# USBGpib_biggercomponents.net
KiCad netlist of a schematic drawn in EAGLE
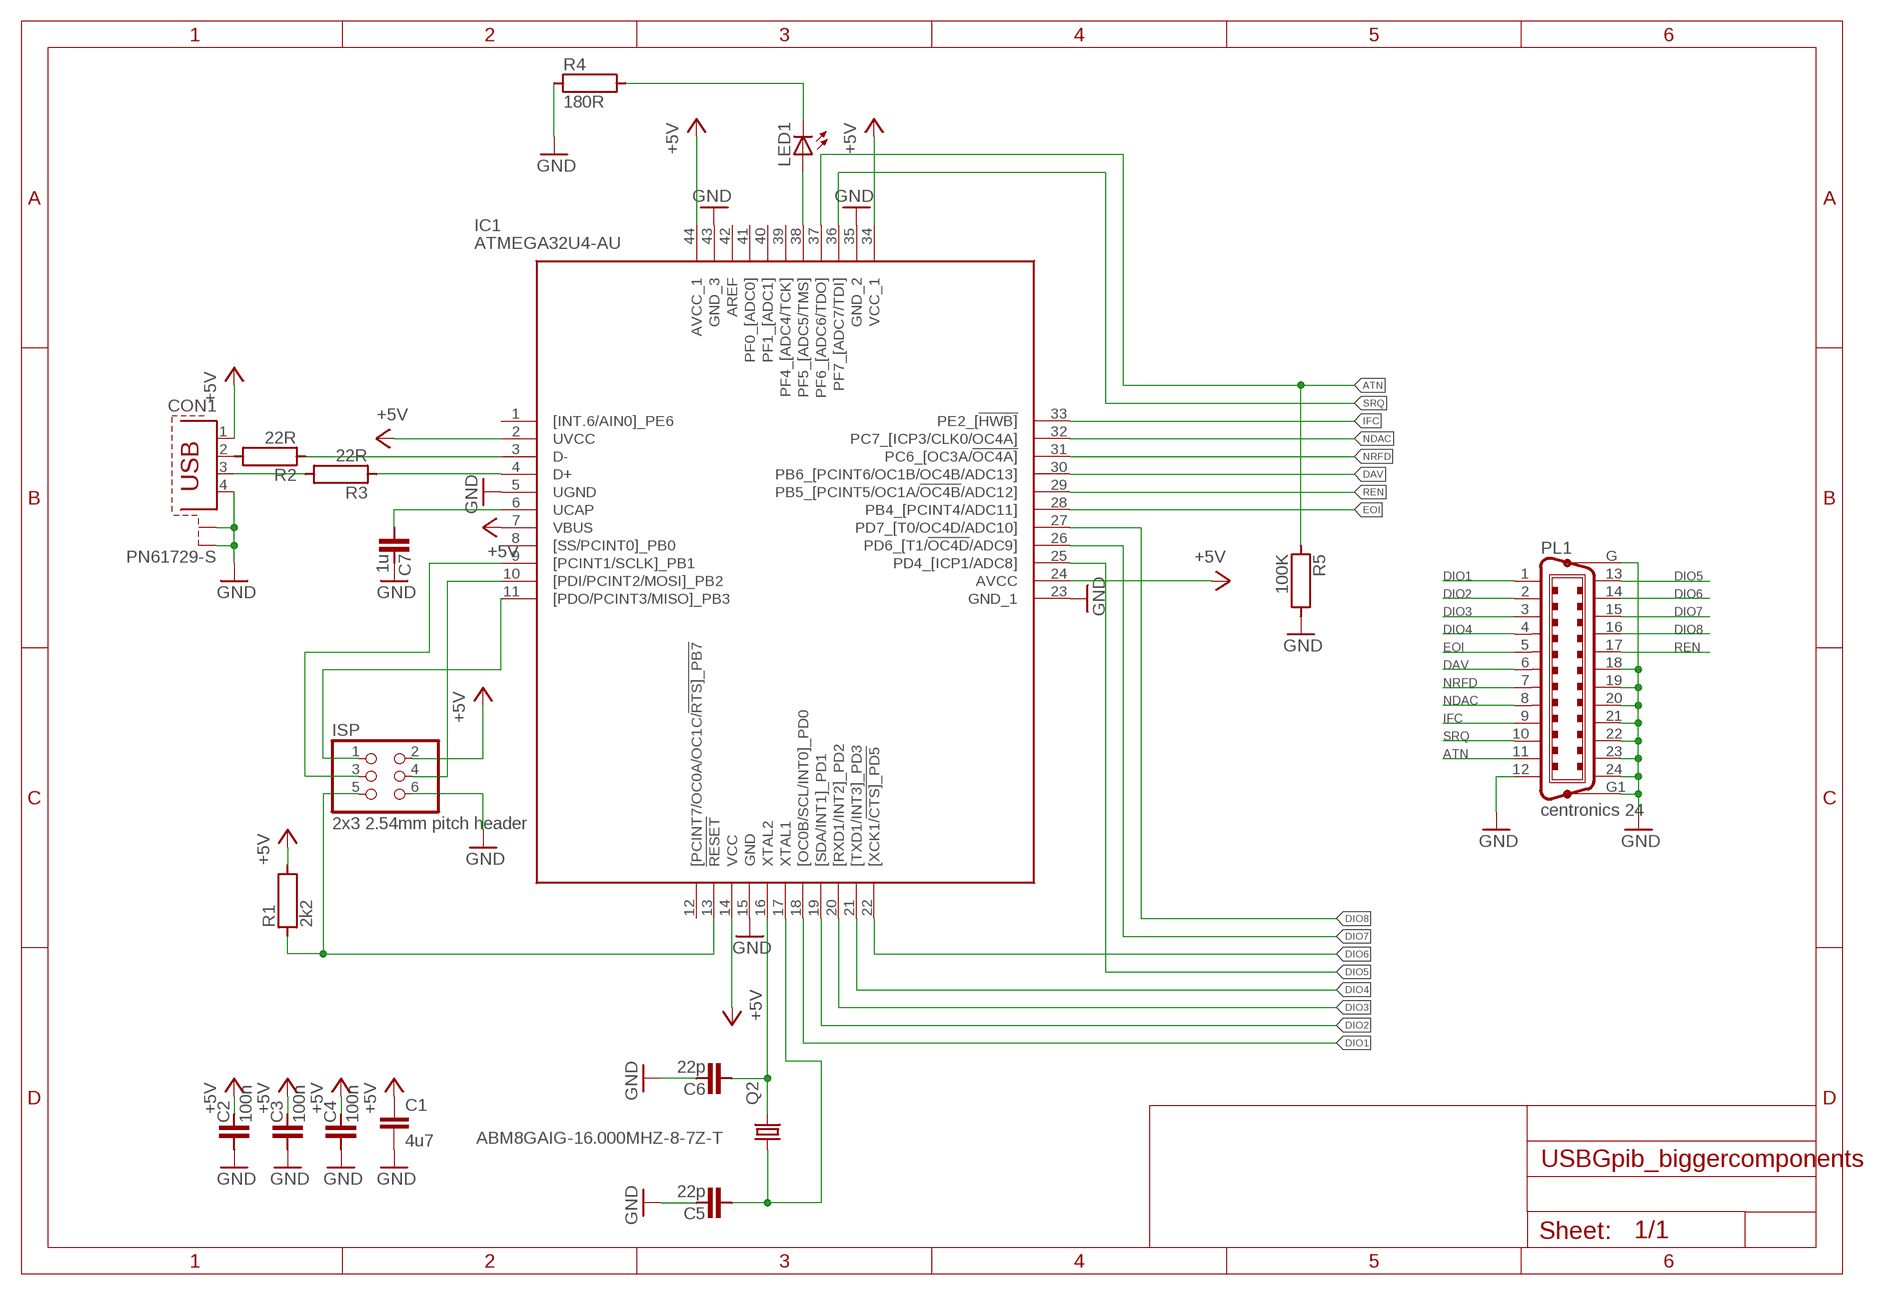
[diagram p0: schematic, sheet 1]

(export (version "E")
  (design (tool "Eeschema 10.0.6"))
  (components
    (comp (ref "C1")
      (value "4u7")
      (footprint "eagle-import:C0805")
      (libsource (lib "eagle-import") (part "C-EUC0805"))
    )
    (comp (ref "C2")
      (value "100n")
      (footprint "eagle-import:C0603")
      (libsource (lib "eagle-import") (part "C0603"))
    )
    (comp (ref "C3")
      (value "100n")
      (footprint "eagle-import:C0603")
      (libsource (lib "eagle-import") (part "C0603"))
    )
    (comp (ref "C4")
      (value "100n")
      (footprint "eagle-import:C0603")
      (libsource (lib "eagle-import") (part "C0603"))
    )
    (comp (ref "C5")
      (value "22p")
      (footprint "eagle-import:C0603")
      (libsource (lib "eagle-import") (part "C0603"))
    )
    (comp (ref "C6")
      (value "22p")
      (footprint "eagle-import:C0603")
      (libsource (lib "eagle-import") (part "C0603"))
    )
    (comp (ref "C7")
      (value "1u")
      (footprint "eagle-import:C0603")
      (libsource (lib "eagle-import") (part "C0603"))
    )
    (comp (ref "CON1")
      (value "PN61729-S")
      (footprint "eagle-import:PN61729-S")
      (libsource (lib "eagle-import") (part "PN61729-S"))
    )
    (comp (ref "IC1")
      (value "ATMEGA32U4-AU")
      (footprint "eagle-import:QFP80P1200X1200X120-44N")
      (fields
        (field (name "MANUFACTURER_PART_NUMBER") "ATMEGA16U4-AU")
        (field (name "MOUSER_PART_NUMBER") "556-ATMEGA16U4-AU")
        (field (name "RS_PART_NUMBER") "1773649P")
      )
      (libsource (lib "eagle-import") (part "ATMEGA16U4-AU"))
    )
    (comp (ref "ISP")
      (value "2x3 2.54mm pitch header")
      (footprint "eagle-import:2X03")
      (libsource (lib "eagle-import") (part "PINHD-2X3"))
    )
    (comp (ref "LED1")
      (value "LEDCHIPLED_1206")
      (footprint "eagle-import:CHIPLED_1206")
      (libsource (lib "eagle-import") (part "LEDCHIPLED_1206"))
    )
    (comp (ref "PL1")
      (value "centronics 24")
      (footprint "eagle-import:24HP_MALE")
      (libsource (lib "eagle-import") (part "C24HPMALE"))
    )
    (comp (ref "Q2")
      (value "ABM8GAIG-16.000MHZ-8-7Z-T")
      (footprint "eagle-import:3.2X2.5_KX-7")
      (libsource (lib "eagle-import") (part "KX-7"))
    )
    (comp (ref "R1")
      (value "2k2")
      (footprint "eagle-import:R0603")
      (libsource (lib "eagle-import") (part "R0603"))
    )
    (comp (ref "R2")
      (value "22R")
      (footprint "eagle-import:R0603")
      (libsource (lib "eagle-import") (part "R0603"))
    )
    (comp (ref "R3")
      (value "22R")
      (footprint "eagle-import:R0603")
      (libsource (lib "eagle-import") (part "R0603"))
    )
    (comp (ref "R4")
      (value "180R")
      (footprint "eagle-import:R0603")
      (libsource (lib "eagle-import") (part "R0603"))
    )
    (comp (ref "R5")
      (value "100K")
      (footprint "eagle-import:R0603")
      (libsource (lib "eagle-import") (part "R0603"))
    )
  )
  (nets
    (net (code "1") (name "+5V") (class "Default")
      (node (ref "C1") (pin "1") (pinfunction "1_1") (pintype "passive"))
      (node (ref "C2") (pin "2") (pinfunction "2_2") (pintype "passive"))
      (node (ref "C3") (pin "2") (pinfunction "2_2") (pintype "passive"))
      (node (ref "C4") (pin "2") (pinfunction "2_2") (pintype "passive"))
      (node (ref "CON1") (pin "1") (pinfunction "1_1") (pintype "passive"))
      (node (ref "IC1") (pin "14") (pinfunction "VCC_14") (pintype "power_in"))
      (node (ref "IC1") (pin "2") (pinfunction "UVCC_2") (pintype "power_in"))
      (node (ref "IC1") (pin "24") (pinfunction "AVCC_24") (pintype "power_in"))
      (node (ref "IC1") (pin "34") (pinfunction "VCC_1_34") (pintype "power_in"))
      (node (ref "IC1") (pin "44") (pinfunction "AVCC_1_44") (pintype "power_in"))
      (node (ref "IC1") (pin "7") (pinfunction "VBUS_7") (pintype "bidirectional"))
      (node (ref "ISP") (pin "2") (pinfunction "2_2") (pintype "passive"))
      (node (ref "R1") (pin "2") (pinfunction "2_2") (pintype "passive"))
    )
    (net (code "2") (name "ATN") (class "Default")
      (node (ref "IC1") (pin "37") (pinfunction "PF6_[ADC6/TDO]_37") (pintype "bidirectional"))
      (node (ref "PL1") (pin "11") (pinfunction "11_11") (pintype "passive"))
      (node (ref "R5") (pin "1") (pinfunction "1_1") (pintype "passive"))
    )
    (net (code "3") (name "DAV") (class "Default")
      (node (ref "IC1") (pin "30") (pinfunction "PB6_[PCINT6/OC1B/OC4B/ADC13]_30") (pintype "input"))
      (node (ref "PL1") (pin "6") (pinfunction "6_6") (pintype "passive"))
    )
    (net (code "4") (name "DIO1") (class "Default")
      (node (ref "IC1") (pin "18") (pinfunction "[OC0B/SCL/INT0]_PD0_18") (pintype "input"))
      (node (ref "PL1") (pin "1") (pinfunction "1_1") (pintype "passive"))
    )
    (net (code "5") (name "DIO2") (class "Default")
      (node (ref "IC1") (pin "19") (pinfunction "[SDA/INT1]_PD1_19") (pintype "input"))
      (node (ref "PL1") (pin "2") (pinfunction "2_2") (pintype "passive"))
    )
    (net (code "6") (name "DIO3") (class "Default")
      (node (ref "IC1") (pin "20") (pinfunction "[RXD1/INT2]_PD2_20") (pintype "input"))
      (node (ref "PL1") (pin "3") (pinfunction "3_3") (pintype "passive"))
    )
    (net (code "7") (name "DIO4") (class "Default")
      (node (ref "IC1") (pin "21") (pinfunction "[TXD1/INT3]_PD3_21") (pintype "input"))
      (node (ref "PL1") (pin "4") (pinfunction "4_4") (pintype "passive"))
    )
    (net (code "8") (name "DIO5") (class "Default")
      (node (ref "IC1") (pin "25") (pinfunction "PD4_[ICP1/ADC8]_25") (pintype "bidirectional"))
      (node (ref "PL1") (pin "13") (pinfunction "13_13") (pintype "passive"))
    )
    (net (code "9") (name "DIO6") (class "Default")
      (node (ref "IC1") (pin "22") (pinfunction "[XCK1/~{CTS]_PD5}_22") (pintype "bidirectional"))
      (node (ref "PL1") (pin "14") (pinfunction "14_14") (pintype "passive"))
    )
    (net (code "10") (name "DIO7") (class "Default")
      (node (ref "IC1") (pin "26") (pinfunction "PD6_[T1/~{OC4D}/ADC9]_26") (pintype "bidirectional"))
      (node (ref "PL1") (pin "15") (pinfunction "15_15") (pintype "passive"))
    )
    (net (code "11") (name "DIO8") (class "Default")
      (node (ref "IC1") (pin "27") (pinfunction "PD7_[T0/OC4D/ADC10]_27") (pintype "bidirectional"))
      (node (ref "PL1") (pin "16") (pinfunction "16_16") (pintype "passive"))
    )
    (net (code "12") (name "EOI") (class "Default")
      (node (ref "IC1") (pin "28") (pinfunction "PB4_[PCINT4/ADC11]_28") (pintype "input"))
      (node (ref "PL1") (pin "5") (pinfunction "5_5") (pintype "passive"))
    )
    (net (code "13") (name "GND") (class "Default")
      (node (ref "C1") (pin "2") (pinfunction "2_2") (pintype "passive"))
      (node (ref "C2") (pin "1") (pinfunction "1_1") (pintype "passive"))
      (node (ref "C3") (pin "1") (pinfunction "1_1") (pintype "passive"))
      (node (ref "C4") (pin "1") (pinfunction "1_1") (pintype "passive"))
      (node (ref "C5") (pin "2") (pinfunction "2_2") (pintype "passive"))
      (node (ref "C6") (pin "2") (pinfunction "2_2") (pintype "passive"))
      (node (ref "C7") (pin "2") (pinfunction "2_2") (pintype "passive"))
      (node (ref "CON1") (pin "4") (pinfunction "4_4") (pintype "passive"))
      (node (ref "CON1") (pin "S1") (pinfunction "S1_S1") (pintype "passive"))
      (node (ref "CON1") (pin "S2") (pinfunction "S2_S2") (pintype "passive"))
      (node (ref "IC1") (pin "15") (pinfunction "GND_15") (pintype "power_in"))
      (node (ref "IC1") (pin "23") (pinfunction "GND_1_23") (pintype "power_in"))
      (node (ref "IC1") (pin "35") (pinfunction "GND_2_35") (pintype "power_in"))
      (node (ref "IC1") (pin "43") (pinfunction "GND_3_43") (pintype "power_in"))
      (node (ref "IC1") (pin "5") (pinfunction "UGND_5") (pintype "power_in"))
      (node (ref "ISP") (pin "6") (pinfunction "6_6") (pintype "passive"))
      (node (ref "PL1") (pin "12") (pinfunction "12_12") (pintype "passive"))
      (node (ref "PL1") (pin "18") (pinfunction "18_18") (pintype "passive"))
      (node (ref "PL1") (pin "19") (pinfunction "19_19") (pintype "passive"))
      (node (ref "PL1") (pin "20") (pinfunction "20_20") (pintype "passive"))
      (node (ref "PL1") (pin "21") (pinfunction "21_21") (pintype "passive"))
      (node (ref "PL1") (pin "22") (pinfunction "22_22") (pintype "passive"))
      (node (ref "PL1") (pin "23") (pinfunction "23_23") (pintype "passive"))
      (node (ref "PL1") (pin "24") (pinfunction "24_24") (pintype "passive"))
      (node (ref "PL1") (pin "G") (pinfunction "G_G") (pintype "passive"))
      (node (ref "PL1") (pin "G1") (pinfunction "G1_G1") (pintype "passive"))
      (node (ref "R4") (pin "1") (pinfunction "1_1") (pintype "passive"))
      (node (ref "R5") (pin "2") (pinfunction "2_2") (pintype "passive"))
    )
    (net (code "14") (name "IFC") (class "Default")
      (node (ref "IC1") (pin "33") (pinfunction "PE2_[~{HWB]}_33") (pintype "bidirectional"))
      (node (ref "PL1") (pin "9") (pinfunction "9_9") (pintype "passive"))
    )
    (net (code "15") (name "NDAC") (class "Default")
      (node (ref "IC1") (pin "32") (pinfunction "PC7_[ICP3/CLK0/OC4A]_32") (pintype "input"))
      (node (ref "PL1") (pin "8") (pinfunction "8_8") (pintype "passive"))
    )
    (net (code "16") (name "NRFD") (class "Default")
      (node (ref "IC1") (pin "31") (pinfunction "PC6_[OC3A/~{OC4A]}_31") (pintype "bidirectional"))
      (node (ref "PL1") (pin "7") (pinfunction "7_7") (pintype "passive"))
    )
    (net (code "17") (name "Net-(CON1-Pad2)") (class "Default")
      (node (ref "CON1") (pin "2") (pinfunction "2_2") (pintype "passive"))
      (node (ref "R2") (pin "2") (pinfunction "2_2") (pintype "passive"))
    )
    (net (code "18") (name "Net-(CON1-Pad3)") (class "Default")
      (node (ref "CON1") (pin "3") (pinfunction "3_3") (pintype "passive"))
      (node (ref "R3") (pin "2") (pinfunction "2_2") (pintype "passive"))
    )
    (net (code "19") (name "Net-(IC1-D+)") (class "Default")
      (node (ref "IC1") (pin "4") (pinfunction "D+_4") (pintype "bidirectional"))
      (node (ref "R3") (pin "1") (pinfunction "1_1") (pintype "passive"))
    )
    (net (code "20") (name "Net-(IC1-D-)") (class "Default")
      (node (ref "IC1") (pin "3") (pinfunction "D-_3") (pintype "bidirectional"))
      (node (ref "R2") (pin "1") (pinfunction "1_1") (pintype "passive"))
    )
    (net (code "21") (name "Net-(IC1-PF5_[ADC5{slash}TMS])") (class "Default")
      (node (ref "IC1") (pin "38") (pinfunction "PF5_[ADC5/TMS]_38") (pintype "bidirectional"))
      (node (ref "LED1") (pin "A") (pinfunction "A_A") (pintype "passive"))
    )
    (net (code "22") (name "Net-(IC1-UCAP)") (class "Default")
      (node (ref "C7") (pin "1") (pinfunction "1_1") (pintype "passive"))
      (node (ref "IC1") (pin "6") (pinfunction "UCAP_6") (pintype "bidirectional"))
    )
    (net (code "23") (name "Net-(IC1-XTAL1)") (class "Default")
      (node (ref "C5") (pin "1") (pinfunction "1_1") (pintype "passive"))
      (node (ref "IC1") (pin "17") (pinfunction "XTAL1_17") (pintype "bidirectional"))
      (node (ref "Q2") (pin "1") (pinfunction "1_1") (pintype "passive"))
    )
    (net (code "24") (name "Net-(IC1-XTAL2)") (class "Default")
      (node (ref "C6") (pin "1") (pinfunction "1_1") (pintype "passive"))
      (node (ref "IC1") (pin "16") (pinfunction "XTAL2_16") (pintype "bidirectional"))
      (node (ref "Q2") (pin "3") (pinfunction "2_3") (pintype "passive"))
    )
    (net (code "25") (name "Net-(IC1-[PCINT1{slash}SCLK]_PB1)") (class "Default")
      (node (ref "IC1") (pin "9") (pinfunction "[PCINT1/SCLK]_PB1_9") (pintype "input"))
      (node (ref "ISP") (pin "3") (pinfunction "3_3") (pintype "passive"))
    )
    (net (code "26") (name "Net-(IC1-[PDI{slash}PCINT2{slash}MOSI]_PB2)") (class "Default")
      (node (ref "IC1") (pin "10") (pinfunction "[PDI/PCINT2/MOSI]_PB2_10") (pintype "input"))
      (node (ref "ISP") (pin "4") (pinfunction "4_4") (pintype "passive"))
    )
    (net (code "27") (name "Net-(IC1-[PDO{slash}PCINT3{slash}MISO]_PB3)") (class "Default")
      (node (ref "IC1") (pin "11") (pinfunction "[PDO/PCINT3/MISO]_PB3_11") (pintype "input"))
      (node (ref "ISP") (pin "1") (pinfunction "1_1") (pintype "passive"))
    )
    (net (code "28") (name "Net-(IC1-~{RESET})") (class "Default")
      (node (ref "IC1") (pin "13") (pinfunction "~{RESET}_13") (pintype "bidirectional"))
      (node (ref "ISP") (pin "5") (pinfunction "5_5") (pintype "passive"))
      (node (ref "R1") (pin "1") (pinfunction "1_1") (pintype "passive"))
    )
    (net (code "29") (name "Net-(LED1-PadC)") (class "Default")
      (node (ref "LED1") (pin "C") (pinfunction "C_C") (pintype "passive"))
      (node (ref "R4") (pin "2") (pinfunction "2_2") (pintype "passive"))
    )
    (net (code "30") (name "REN") (class "Default")
      (node (ref "IC1") (pin "29") (pinfunction "PB5_[PCINT5/OC1A/~{OC4B}/ADC12]_29") (pintype "input"))
      (node (ref "PL1") (pin "17") (pinfunction "17_17") (pintype "passive"))
    )
    (net (code "31") (name "SRQ") (class "Default")
      (node (ref "IC1") (pin "36") (pinfunction "PF7_[ADC7/TDI]_36") (pintype "bidirectional"))
      (node (ref "PL1") (pin "10") (pinfunction "10_10") (pintype "passive"))
    )
    (net (code "32") (name "unconnected-(IC1-AREF-Pad42)") (class "Default")
      (node (ref "IC1") (pin "42") (pinfunction "AREF_42") (pintype "input"))
    )
    (net (code "33") (name "unconnected-(IC1-PF0_[ADC0]-Pad41)") (class "Default")
      (node (ref "IC1") (pin "41") (pinfunction "PF0_[ADC0]_41") (pintype "bidirectional"))
    )
    (net (code "34") (name "unconnected-(IC1-PF1_[ADC1]-Pad40)") (class "Default")
      (node (ref "IC1") (pin "40") (pinfunction "PF1_[ADC1]_40") (pintype "bidirectional"))
    )
    (net (code "35") (name "unconnected-(IC1-PF4_[ADC4{slash}TCK]-Pad39)") (class "Default")
      (node (ref "IC1") (pin "39") (pinfunction "PF4_[ADC4/TCK]_39") (pintype "bidirectional"))
    )
    (net (code "36") (name "unconnected-(IC1-[INT.6{slash}AIN0]_PE6-Pad1)") (class "Default")
      (node (ref "IC1") (pin "1") (pinfunction "[INT.6/AIN0]_PE6_1") (pintype "input"))
    )
    (net (code "37") (name "unconnected-(IC1-[PCINT7{slash}OC0A{slash}OC1C{slash}~{RTS]_PB7}-Pad12)") (class "Default")
      (node (ref "IC1") (pin "12") (pinfunction "[PCINT7/OC0A/OC1C/~{RTS]_PB7}_12") (pintype "input"))
    )
    (net (code "38") (name "unconnected-(IC1-[SS{slash}PCINT0]_PB0-Pad8)") (class "Default")
      (node (ref "IC1") (pin "8") (pinfunction "[SS/PCINT0]_PB0_8") (pintype "input"))
    )
  )
)
